# Front_panel_owon_ver_mini.net
KiCad netlist of a schematic drawn in EAGLE
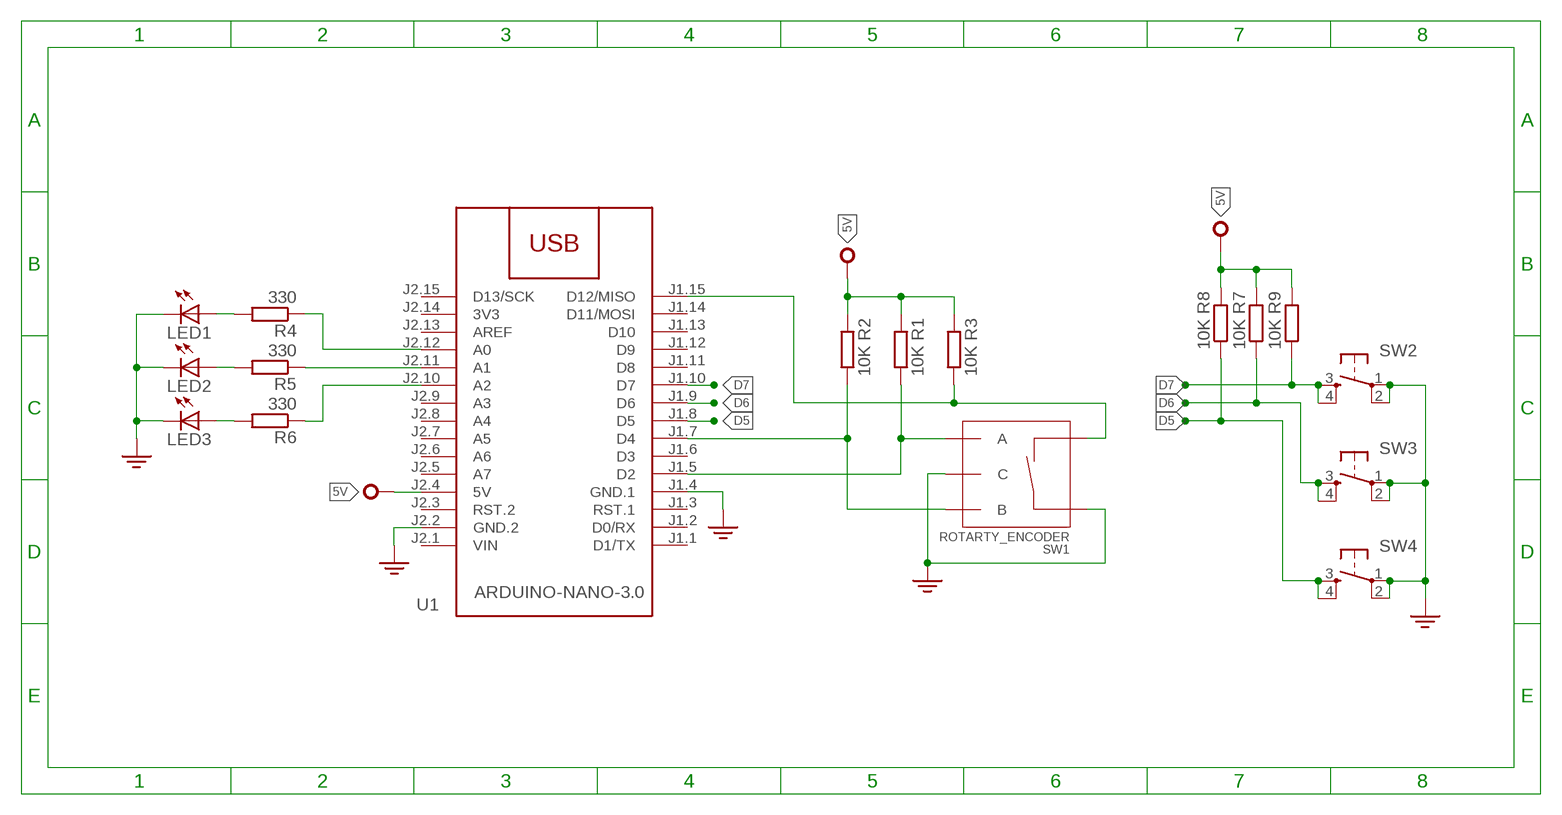
[diagram p0: schematic, sheet 1]

(export (version "E")
  (design (tool "Eeschema 10.0.6"))
  (components
    (comp (ref "LED1")
      (value "LED5MM")
      (footprint "eagle-import:LED5MM")
      (libsource (lib "eagle-import") (part "LED5MM"))
    )
    (comp (ref "LED2")
      (value "LED5MM")
      (footprint "eagle-import:LED5MM")
      (libsource (lib "eagle-import") (part "LED5MM"))
    )
    (comp (ref "LED3")
      (value "LED5MM")
      (footprint "eagle-import:LED5MM")
      (libsource (lib "eagle-import") (part "LED5MM"))
    )
    (comp (ref "R1")
      (value "10K")
      (footprint "eagle-import:0204_7")
      (libsource (lib "eagle-import") (part "R-EU_0204/7"))
    )
    (comp (ref "R2")
      (value "10K")
      (footprint "eagle-import:0204_7")
      (libsource (lib "eagle-import") (part "R-EU_0204/7"))
    )
    (comp (ref "R3")
      (value "10K")
      (footprint "eagle-import:0204_7")
      (libsource (lib "eagle-import") (part "R-EU_0204/7"))
    )
    (comp (ref "R4")
      (value "330")
      (footprint "eagle-import:0204_7")
      (libsource (lib "eagle-import") (part "R-EU_0204/7"))
    )
    (comp (ref "R5")
      (value "330")
      (footprint "eagle-import:0204_7")
      (libsource (lib "eagle-import") (part "R-EU_0204/7"))
    )
    (comp (ref "R6")
      (value "330")
      (footprint "eagle-import:0204_7")
      (libsource (lib "eagle-import") (part "R-EU_0204/7"))
    )
    (comp (ref "R7")
      (value "10K")
      (footprint "eagle-import:0204_7")
      (libsource (lib "eagle-import") (part "R-EU_0204/7"))
    )
    (comp (ref "R8")
      (value "10K")
      (footprint "eagle-import:0204_7")
      (libsource (lib "eagle-import") (part "R-EU_0204/7"))
    )
    (comp (ref "R9")
      (value "10K")
      (footprint "eagle-import:0204_7")
      (libsource (lib "eagle-import") (part "R-EU_0204/7"))
    )
    (comp (ref "SW1")
      (value "ROTARTY_ENCODER")
      (footprint "eagle-import:ROTARY_ENC_PLAIN")
      (libsource (lib "eagle-import") (part "ROTARTY_ENCODER"))
    )
    (comp (ref "SW2")
      (value "TACTILE-SWITCH-PTH")
      (footprint "eagle-import:TAC-SWITCH-PTH")
      (libsource (lib "eagle-import") (part "TACTILE-SWITCH-PTH"))
    )
    (comp (ref "SW3")
      (value "TACTILE-SWITCH-PTH")
      (footprint "eagle-import:TAC-SWITCH-PTH")
      (libsource (lib "eagle-import") (part "TACTILE-SWITCH-PTH"))
    )
    (comp (ref "SW4")
      (value "TACTILE-SWITCH-PTH")
      (footprint "eagle-import:TAC-SWITCH-PTH")
      (libsource (lib "eagle-import") (part "TACTILE-SWITCH-PTH"))
    )
    (comp (ref "U1")
      (value "ARDUINO-NANO-3.0")
      (footprint "eagle-import:ARDUINO-NANO-3.0")
      (libsource (lib "eagle-import") (part "ARDUINO-NANO-3.0"))
    )
  )
  (nets
    (net (code "1") (name "/3V3") (class "Default")
      (node (ref "U1") (pin "J2.14") (pinfunction "3V3_J2.14") (pintype "power_in"))
    )
    (net (code "2") (name "/VIN") (class "Default")
      (node (ref "U1") (pin "J2.1") (pinfunction "VIN_J2.1") (pintype "power_in"))
    )
    (net (code "3") (name "5V") (class "Default")
      (node (ref "R1") (pin "2") (pinfunction "2_2") (pintype "passive"))
      (node (ref "R2") (pin "2") (pinfunction "2_2") (pintype "passive"))
      (node (ref "R3") (pin "2") (pinfunction "2_2") (pintype "passive"))
      (node (ref "R7") (pin "2") (pinfunction "2_2") (pintype "passive"))
      (node (ref "R8") (pin "2") (pinfunction "2_2") (pintype "passive"))
      (node (ref "R9") (pin "2") (pinfunction "2_2") (pintype "passive"))
      (node (ref "U1") (pin "J2.4") (pinfunction "5V_J2.4") (pintype "power_in"))
    )
    (net (code "4") (name "D5") (class "Default")
      (node (ref "R8") (pin "1") (pinfunction "1_1") (pintype "passive"))
      (node (ref "SW4") (pin "3") (pinfunction "3_3") (pintype "passive"))
      (node (ref "SW4") (pin "4") (pinfunction "4_4") (pintype "passive"))
      (node (ref "U1") (pin "J1.8") (pinfunction "D5_J1.8") (pintype "bidirectional"))
    )
    (net (code "5") (name "D6") (class "Default")
      (node (ref "R7") (pin "1") (pinfunction "1_1") (pintype "passive"))
      (node (ref "SW3") (pin "3") (pinfunction "3_3") (pintype "passive"))
      (node (ref "SW3") (pin "4") (pinfunction "4_4") (pintype "passive"))
      (node (ref "U1") (pin "J1.9") (pinfunction "D6_J1.9") (pintype "bidirectional"))
    )
    (net (code "6") (name "D7") (class "Default")
      (node (ref "R9") (pin "1") (pinfunction "1_1") (pintype "passive"))
      (node (ref "SW2") (pin "3") (pinfunction "3_3") (pintype "passive"))
      (node (ref "SW2") (pin "4") (pinfunction "4_4") (pintype "passive"))
      (node (ref "U1") (pin "J1.10") (pinfunction "D7_J1.10") (pintype "bidirectional"))
    )
    (net (code "7") (name "GND2") (class "Default")
      (node (ref "LED1") (pin "K") (pinfunction "C_K") (pintype "passive"))
      (node (ref "LED2") (pin "K") (pinfunction "C_K") (pintype "passive"))
      (node (ref "LED3") (pin "K") (pinfunction "C_K") (pintype "passive"))
      (node (ref "SW1") (pin "C") (pinfunction "C_C") (pintype "bidirectional"))
      (node (ref "SW1") (pin "SW+") (pinfunction "SW+_SW+") (pintype "bidirectional"))
      (node (ref "SW2") (pin "1") (pinfunction "1_1") (pintype "passive"))
      (node (ref "SW2") (pin "2") (pinfunction "2_2") (pintype "passive"))
      (node (ref "SW3") (pin "1") (pinfunction "1_1") (pintype "passive"))
      (node (ref "SW3") (pin "2") (pinfunction "2_2") (pintype "passive"))
      (node (ref "SW4") (pin "1") (pinfunction "1_1") (pintype "passive"))
      (node (ref "SW4") (pin "2") (pinfunction "2_2") (pintype "passive"))
      (node (ref "U1") (pin "J1.4") (pinfunction "GND.1_J1.4") (pintype "power_in"))
      (node (ref "U1") (pin "J2.2") (pinfunction "GND.2_J2.2") (pintype "power_in"))
    )
    (net (code "8") (name "Net-(LED1-PadA)") (class "Default")
      (node (ref "LED1") (pin "A") (pinfunction "A_A") (pintype "passive"))
      (node (ref "R4") (pin "2") (pinfunction "2_2") (pintype "passive"))
    )
    (net (code "9") (name "Net-(LED2-PadA)") (class "Default")
      (node (ref "LED2") (pin "A") (pinfunction "A_A") (pintype "passive"))
      (node (ref "R5") (pin "2") (pinfunction "2_2") (pintype "passive"))
    )
    (net (code "10") (name "Net-(LED3-PadA)") (class "Default")
      (node (ref "LED3") (pin "A") (pinfunction "A_A") (pintype "passive"))
      (node (ref "R6") (pin "2") (pinfunction "2_2") (pintype "passive"))
    )
    (net (code "11") (name "Net-(U1-A0)") (class "Default")
      (node (ref "R4") (pin "1") (pinfunction "1_1") (pintype "passive"))
      (node (ref "U1") (pin "J2.12") (pinfunction "A0_J2.12") (pintype "bidirectional"))
    )
    (net (code "12") (name "Net-(U1-A1)") (class "Default")
      (node (ref "R5") (pin "1") (pinfunction "1_1") (pintype "passive"))
      (node (ref "U1") (pin "J2.11") (pinfunction "A1_J2.11") (pintype "bidirectional"))
    )
    (net (code "13") (name "Net-(U1-A2)") (class "Default")
      (node (ref "R6") (pin "1") (pinfunction "1_1") (pintype "passive"))
      (node (ref "U1") (pin "J2.10") (pinfunction "A2_J2.10") (pintype "bidirectional"))
    )
    (net (code "14") (name "Net-(U1-D2)") (class "Default")
      (node (ref "R1") (pin "1") (pinfunction "1_1") (pintype "passive"))
      (node (ref "SW1") (pin "A") (pinfunction "A_A") (pintype "bidirectional"))
      (node (ref "U1") (pin "J1.5") (pinfunction "D2_J1.5") (pintype "bidirectional"))
    )
    (net (code "15") (name "Net-(U1-D4)") (class "Default")
      (node (ref "R2") (pin "1") (pinfunction "1_1") (pintype "passive"))
      (node (ref "SW1") (pin "B") (pinfunction "B_B") (pintype "bidirectional"))
      (node (ref "U1") (pin "J1.7") (pinfunction "D4_J1.7") (pintype "bidirectional"))
    )
    (net (code "16") (name "Net-(U1-D12{slash}MISO)") (class "Default")
      (node (ref "R3") (pin "1") (pinfunction "1_1") (pintype "passive"))
      (node (ref "SW1") (pin "SW-") (pinfunction "SW-_SW-") (pintype "bidirectional"))
      (node (ref "U1") (pin "J1.15") (pinfunction "D12/MISO_J1.15") (pintype "bidirectional"))
    )
    (net (code "17") (name "unconnected-(U1-A3-PadJ2.9)") (class "Default")
      (node (ref "U1") (pin "J2.9") (pinfunction "A3_J2.9") (pintype "bidirectional"))
    )
    (net (code "18") (name "unconnected-(U1-A4-PadJ2.8)") (class "Default")
      (node (ref "U1") (pin "J2.8") (pinfunction "A4_J2.8") (pintype "bidirectional"))
    )
    (net (code "19") (name "unconnected-(U1-A5-PadJ2.7)") (class "Default")
      (node (ref "U1") (pin "J2.7") (pinfunction "A5_J2.7") (pintype "bidirectional"))
    )
    (net (code "20") (name "unconnected-(U1-A6-PadJ2.6)") (class "Default")
      (node (ref "U1") (pin "J2.6") (pinfunction "A6_J2.6") (pintype "bidirectional"))
    )
    (net (code "21") (name "unconnected-(U1-A7-PadJ2.5)") (class "Default")
      (node (ref "U1") (pin "J2.5") (pinfunction "A7_J2.5") (pintype "bidirectional"))
    )
    (net (code "22") (name "unconnected-(U1-AREF-PadJ2.13)") (class "Default")
      (node (ref "U1") (pin "J2.13") (pinfunction "AREF_J2.13") (pintype "bidirectional"))
    )
    (net (code "23") (name "unconnected-(U1-D0{slash}RX-PadJ1.2)") (class "Default")
      (node (ref "U1") (pin "J1.2") (pinfunction "D0/RX_J1.2") (pintype "bidirectional"))
    )
    (net (code "24") (name "unconnected-(U1-D1{slash}TX-PadJ1.1)") (class "Default")
      (node (ref "U1") (pin "J1.1") (pinfunction "D1/TX_J1.1") (pintype "bidirectional"))
    )
    (net (code "25") (name "unconnected-(U1-D3-PadJ1.6)") (class "Default")
      (node (ref "U1") (pin "J1.6") (pinfunction "D3_J1.6") (pintype "bidirectional"))
    )
    (net (code "26") (name "unconnected-(U1-D8-PadJ1.11)") (class "Default")
      (node (ref "U1") (pin "J1.11") (pinfunction "D8_J1.11") (pintype "bidirectional"))
    )
    (net (code "27") (name "unconnected-(U1-D9-PadJ1.12)") (class "Default")
      (node (ref "U1") (pin "J1.12") (pinfunction "D9_J1.12") (pintype "bidirectional"))
    )
    (net (code "28") (name "unconnected-(U1-D10-PadJ1.13)") (class "Default")
      (node (ref "U1") (pin "J1.13") (pinfunction "D10_J1.13") (pintype "bidirectional"))
    )
    (net (code "29") (name "unconnected-(U1-D11{slash}MOSI-PadJ1.14)") (class "Default")
      (node (ref "U1") (pin "J1.14") (pinfunction "D11/MOSI_J1.14") (pintype "bidirectional"))
    )
    (net (code "30") (name "unconnected-(U1-D13{slash}SCK-PadJ2.15)") (class "Default")
      (node (ref "U1") (pin "J2.15") (pinfunction "D13/SCK_J2.15") (pintype "bidirectional"))
    )
    (net (code "31") (name "unconnected-(U1-RST.1-PadJ1.3)") (class "Default")
      (node (ref "U1") (pin "J1.3") (pinfunction "RST.1_J1.3") (pintype "bidirectional"))
    )
    (net (code "32") (name "unconnected-(U1-RST.2-PadJ2.3)") (class "Default")
      (node (ref "U1") (pin "J2.3") (pinfunction "RST.2_J2.3") (pintype "bidirectional"))
    )
  )
)
